# MicroMod-Artemis-ProcessorBoard.net
KiCad netlist of a schematic drawn in EAGLE
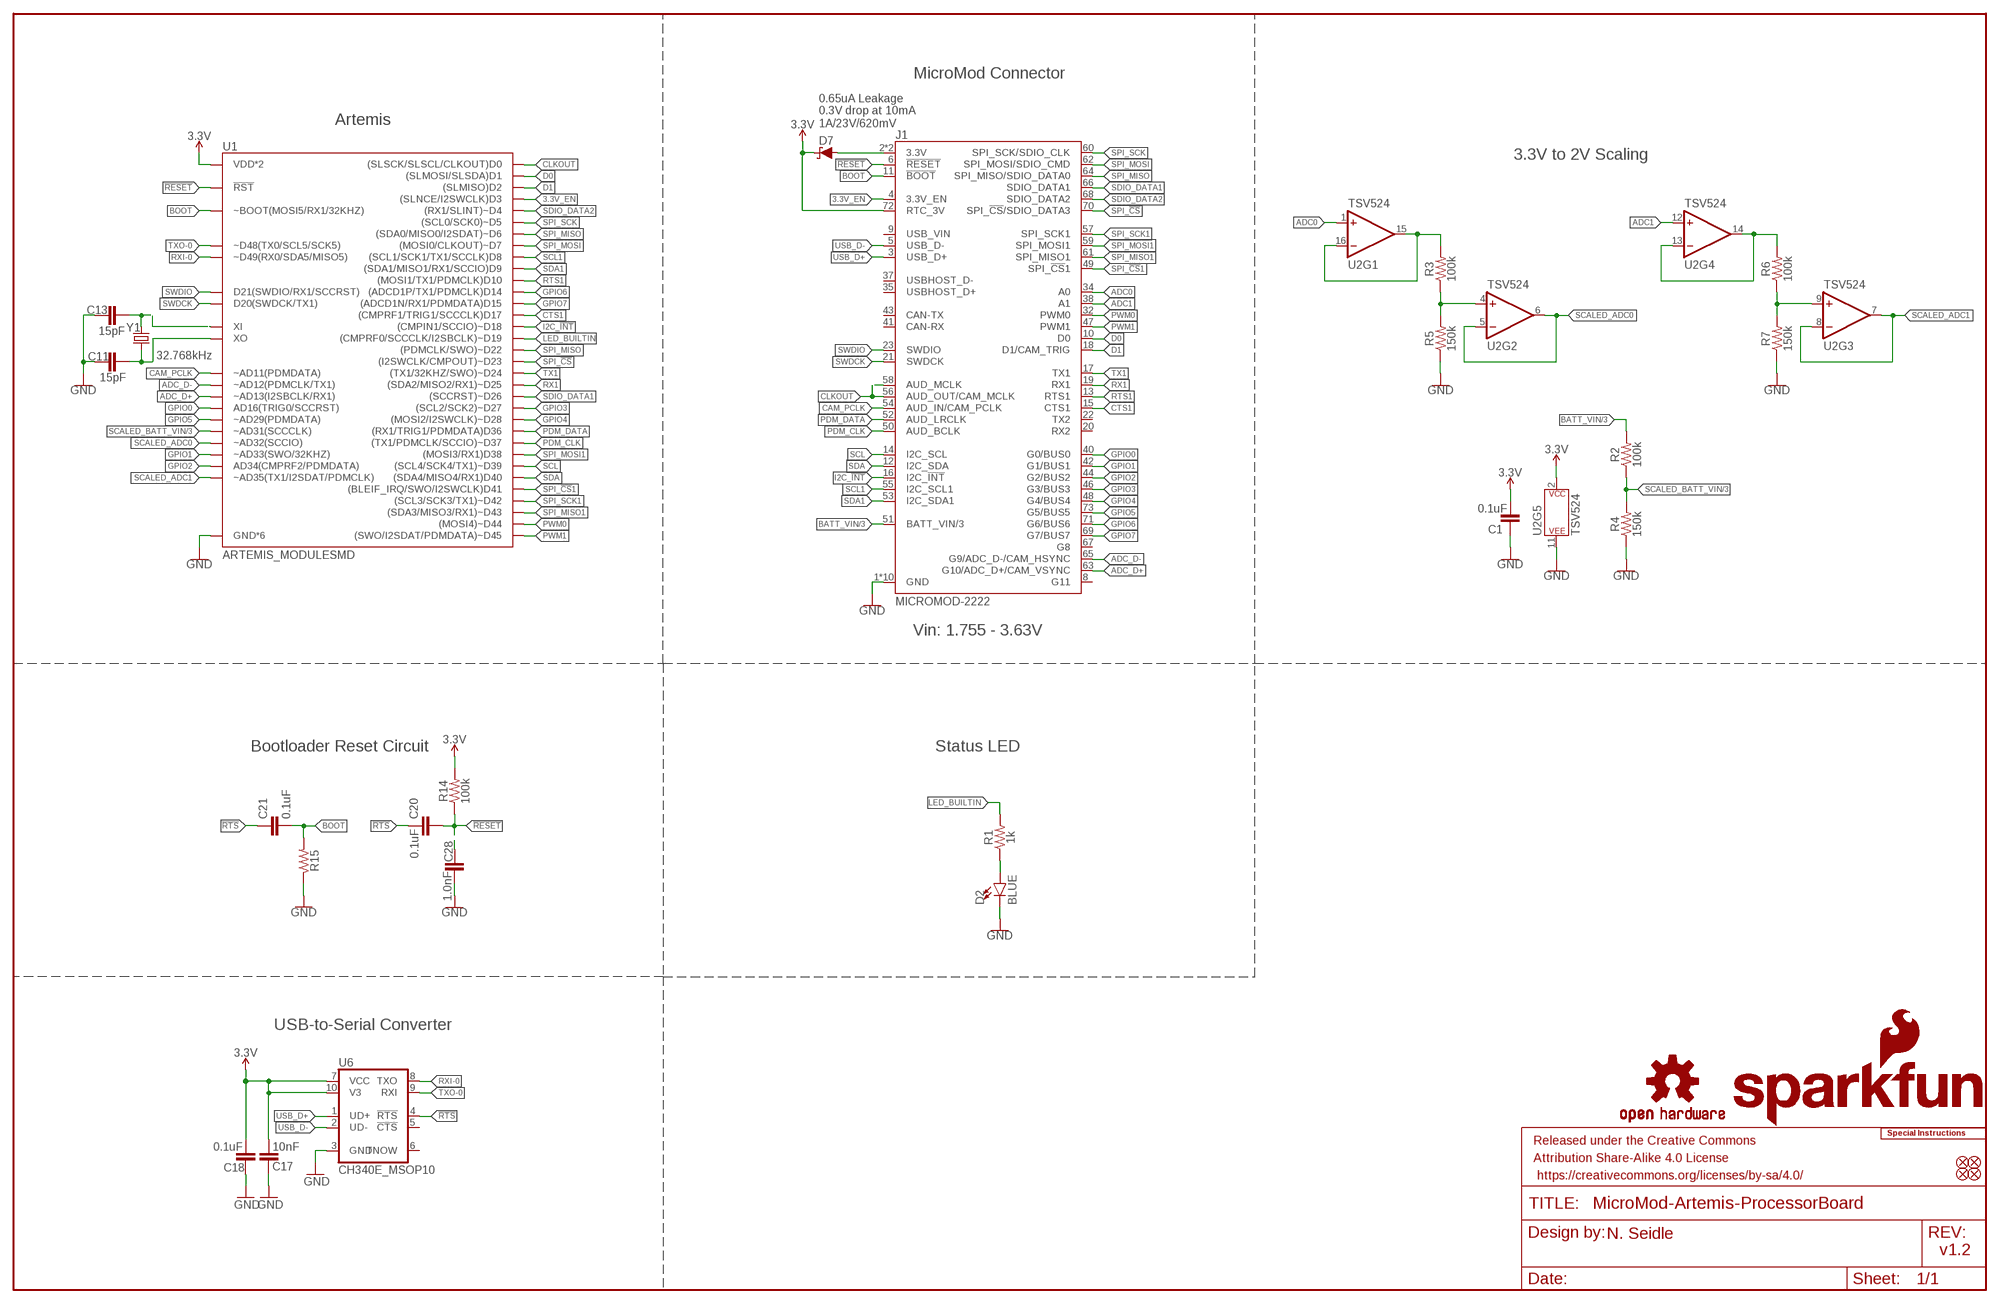
[diagram p0: schematic, sheet 1]

(export (version "E")
  (design (tool "Eeschema 10.0.6"))
  (components
    (comp (ref "C1")
      (value "0.1uF")
      (footprint "eagle-import:0402-TIGHT")
      (libsource (lib "eagle-import") (part "0.1UF-0402T-16V-10%"))
    )
    (comp (ref "C11")
      (value "15pF")
      (footprint "eagle-import:0402-TIGHT")
      (libsource (lib "eagle-import") (part "15PF-0402T-50V-5%"))
    )
    (comp (ref "C13")
      (value "15pF")
      (footprint "eagle-import:0402-TIGHT")
      (libsource (lib "eagle-import") (part "15PF-0402T-50V-5%"))
    )
    (comp (ref "C17")
      (value "10nF")
      (footprint "eagle-import:0402-TIGHT")
      (libsource (lib "eagle-import") (part "10NF-0402T-25V-10%"))
    )
    (comp (ref "C18")
      (value "0.1uF")
      (footprint "eagle-import:0402-TIGHT")
      (libsource (lib "eagle-import") (part "0.1UF-0402T-16V-10%"))
    )
    (comp (ref "C20")
      (value "0.1uF")
      (footprint "eagle-import:0402-TIGHT")
      (libsource (lib "eagle-import") (part "0.1UF-0402T-16V-10%"))
    )
    (comp (ref "C21")
      (value "0.1uF")
      (footprint "eagle-import:0402-TIGHT")
      (libsource (lib "eagle-import") (part "0.1UF-0402T-16V-10%"))
    )
    (comp (ref "C28")
      (value "1.0nF")
      (footprint "eagle-import:0402-TIGHT")
      (libsource (lib "eagle-import") (part "1.0NF/1000PF-0402_TIGHT-50V-10%"))
    )
    (comp (ref "D2")
      (value "BLUE")
      (footprint "eagle-import:LED-0603")
      (libsource (lib "eagle-import") (part "LED-BLUE0603"))
    )
    (comp (ref "D7")
      (value "1A/23V/620mV")
      (footprint "eagle-import:SOD-323")
      (libsource (lib "eagle-import") (part "DIODE-SCHOTTKY-BAT20J"))
    )
    (comp (ref "FD1")
      (value "FIDUCIALUFIDUCIAL")
      (footprint "eagle-import:FIDUCIAL-MICRO")
      (libsource (lib "eagle-import") (part "FIDUCIALUFIDUCIAL"))
    )
    (comp (ref "FD2")
      (value "FIDUCIALUFIDUCIAL")
      (footprint "eagle-import:FIDUCIAL-MICRO")
      (libsource (lib "eagle-import") (part "FIDUCIALUFIDUCIAL"))
    )
    (comp (ref "FD3")
      (value "FIDUCIALUFIDUCIAL")
      (footprint "eagle-import:FIDUCIAL-MICRO")
      (libsource (lib "eagle-import") (part "FIDUCIALUFIDUCIAL"))
    )
    (comp (ref "FD4")
      (value "FIDUCIALUFIDUCIAL")
      (footprint "eagle-import:FIDUCIAL-MICRO")
      (libsource (lib "eagle-import") (part "FIDUCIALUFIDUCIAL"))
    )
    (comp (ref "FRAME1")
      (value "FRAME-LEDGER")
      (footprint "eagle-import:CREATIVE_COMMONS")
      (libsource (lib "eagle-import") (part "FRAME-LEDGER"))
    )
    (comp (ref "J1")
      (value "MICROMOD-2222")
      (footprint "eagle-import:M.2-CARD-E-22")
      (libsource (lib "eagle-import") (part "MICROMOD-2222"))
    )
    (comp (ref "LOGO1")
      (value "SFE_LOGO_NAME_FLAME.1_INCH")
      (footprint "eagle-import:SFE_LOGO_NAME_FLAME_.1")
      (libsource (lib "eagle-import") (part "SFE_LOGO_NAME_FLAME.1_INCH"))
    )
    (comp (ref "LOGO2")
      (value "SFE_LOGO_FLAME.1_INCH")
      (footprint "eagle-import:SFE_LOGO_FLAME_.1")
      (libsource (lib "eagle-import") (part "SFE_LOGO_FLAME.1_INCH"))
    )
    (comp (ref "LOGO3")
      (value "OSHW-LOGOMINI")
      (footprint "eagle-import:OSHW-LOGO-MINI")
      (libsource (lib "eagle-import") (part "OSHW-LOGOMINI"))
    )
    (comp (ref "LOGO4")
      (value "SPECIAL_INSTRUCTIONS-ORDERING")
      (footprint "eagle-import:ORDERING_INSTRUCTIONS")
      (libsource (lib "eagle-import") (part "SPECIAL_INSTRUCTIONS-ORDERING"))
    )
    (comp (ref "R1")
      (value "1k")
      (footprint "eagle-import:0402-TIGHT")
      (libsource (lib "eagle-import") (part "1KOHM-0402T-1/16W-1%"))
    )
    (comp (ref "R2")
      (value "100k")
      (footprint "eagle-import:0402-TIGHT")
      (libsource (lib "eagle-import") (part "100KOHM-0402T-1/16W-1%"))
    )
    (comp (ref "R3")
      (value "100k")
      (footprint "eagle-import:0402-TIGHT")
      (libsource (lib "eagle-import") (part "100KOHM-0402T-1/16W-1%"))
    )
    (comp (ref "R4")
      (value "150k")
      (footprint "eagle-import:0402-TIGHT")
      (libsource (lib "eagle-import") (part "150KOHM-0402T-1/16W-1%"))
    )
    (comp (ref "R5")
      (value "150k")
      (footprint "eagle-import:0402-TIGHT")
      (libsource (lib "eagle-import") (part "150KOHM-0402T-1/16W-1%"))
    )
    (comp (ref "R6")
      (value "100k")
      (footprint "eagle-import:0402-TIGHT")
      (libsource (lib "eagle-import") (part "100KOHM-0402T-1/16W-1%"))
    )
    (comp (ref "R7")
      (value "150k")
      (footprint "eagle-import:0402-TIGHT")
      (libsource (lib "eagle-import") (part "150KOHM-0402T-1/16W-1%"))
    )
    (comp (ref "R14")
      (value "100k")
      (footprint "eagle-import:0402-TIGHT")
      (libsource (lib "eagle-import") (part "100KOHM-0402T-1/16W-1%"))
    )
    (comp (ref "R15")
      (value "220KOHM-0402T-1/16W-1%")
      (footprint "eagle-import:0402-TIGHT")
      (libsource (lib "eagle-import") (part "220KOHM-0402T-1/16W-1%"))
    )
    (comp (ref "U1")
      (value "ARTEMIS_MODULESMD")
      (footprint "eagle-import:ARTEMIS_FP")
      (libsource (lib "eagle-import") (part "ARTEMIS_MODULESMD"))
    )
    (comp (ref "U2")
      (value "TSV524")
      (footprint "eagle-import:QFN-16")
      (libsource (lib "eagle-import") (part "TSV524"))
    )
    (comp (ref "U6")
      (value "CH340E_MSOP10")
      (footprint "eagle-import:MSOP10")
      (libsource (lib "eagle-import") (part "CH340E_MSOP10"))
    )
    (comp (ref "Y1")
      (value "32.768kHz")
      (footprint "eagle-import:CRYSTAL-SMD-3.2X1.5MM")
      (libsource (lib "eagle-import") (part "CRYSTAL-32.768KHZSMD-3.2X1.5"))
    )
  )
  (nets
    (net (code "1") (name "/I2C_~{INT}") (class "Default")
      (node (ref "J1") (pin "16") (pinfunction "I2C_~{INT}_16") (pintype "bidirectional"))
      (node (ref "U1") (pin "~D18") (pinfunction "(CMPIN1/SCCIO)~{D18}_~D18") (pintype "bidirectional"))
    )
    (net (code "2") (name "/SPI_~{CS}") (class "Default")
      (node (ref "J1") (pin "70") (pinfunction "SPI_~{CS}/SDIO_DATA3_70") (pintype "bidirectional"))
      (node (ref "U1") (pin "~D23") (pinfunction "(I2SWCLK/CMPOUT)~{D23}_~D23") (pintype "bidirectional"))
    )
    (net (code "3") (name "/SPI_~{CS}1") (class "Default")
      (node (ref "J1") (pin "49") (pinfunction "SPI_~{CS}1_49") (pintype "bidirectional"))
      (node (ref "U1") (pin "D41") (pinfunction "(BLEIF_IRQ/SWO/I2SWCLK)D41_D41") (pintype "bidirectional"))
    )
    (net (code "4") (name "/~{RESET}") (class "Default")
      (node (ref "C20") (pin "2") (pinfunction "2_2") (pintype "passive"))
      (node (ref "C28") (pin "1") (pinfunction "1_1") (pintype "passive"))
      (node (ref "J1") (pin "6") (pinfunction "~{RESET}_6") (pintype "bidirectional"))
      (node (ref "R14") (pin "1") (pinfunction "1_1") (pintype "passive"))
      (node (ref "U1") (pin "~RST") (pinfunction "~{RST}_~RST") (pintype "bidirectional"))
    )
    (net (code "5") (name "/~{RTS}") (class "Default")
      (node (ref "C20") (pin "1") (pinfunction "1_1") (pintype "passive"))
      (node (ref "C21") (pin "1") (pinfunction "1_1") (pintype "passive"))
      (node (ref "U6") (pin "4") (pinfunction "~{RTS}_4") (pintype "bidirectional"))
    )
    (net (code "6") (name "3.3V") (class "Default")
      (node (ref "C1") (pin "1") (pinfunction "1_1") (pintype "passive"))
      (node (ref "C17") (pin "1") (pinfunction "1_1") (pintype "passive"))
      (node (ref "C18") (pin "1") (pinfunction "1_1") (pintype "passive"))
      (node (ref "D7") (pin "C") (pinfunction "C_C") (pintype "passive"))
      (node (ref "J1") (pin "72") (pinfunction "RTC_3V_72") (pintype "bidirectional"))
      (node (ref "R14") (pin "2") (pinfunction "2_2") (pintype "passive"))
      (node (ref "U1") (pin "VDD@36") (pinfunction "VDD*2_VDD@36") (pintype "bidirectional"))
      (node (ref "U1") (pin "VDD@37") (pinfunction "VDD*2_VDD@37") (pintype "bidirectional"))
      (node (ref "U2") (pin "2") (pinfunction "V+_2") (pintype "bidirectional"))
      (node (ref "U6") (pin "10") (pinfunction "V3_10") (pintype "bidirectional"))
      (node (ref "U6") (pin "7") (pinfunction "VCC_7") (pintype "bidirectional"))
    )
    (net (code "7") (name "3.3V_EN") (class "Default")
      (node (ref "J1") (pin "4") (pinfunction "3.3V_EN_4") (pintype "bidirectional"))
      (node (ref "U1") (pin "D3") (pinfunction "(SLNCE/I2SWCLK)D3_D3") (pintype "bidirectional"))
    )
    (net (code "8") (name "ADC0") (class "Default")
      (node (ref "J1") (pin "34") (pinfunction "A0_34") (pintype "bidirectional"))
      (node (ref "U2") (pin "1") (pinfunction "+IN_1") (pintype "input"))
    )
    (net (code "9") (name "ADC1") (class "Default")
      (node (ref "J1") (pin "38") (pinfunction "A1_38") (pintype "bidirectional"))
      (node (ref "U2") (pin "12") (pinfunction "+IN_12") (pintype "input"))
    )
    (net (code "10") (name "ADC_D+") (class "Default")
      (node (ref "J1") (pin "63") (pinfunction "G10/ADC_D+/CAM_VSYNC_63") (pintype "bidirectional"))
      (node (ref "U1") (pin "~AD13") (pinfunction "~{AD13(I2SBCLK/RX1})_~AD13") (pintype "bidirectional"))
    )
    (net (code "11") (name "ADC_D-") (class "Default")
      (node (ref "J1") (pin "65") (pinfunction "G9/ADC_D-/CAM_HSYNC_65") (pintype "bidirectional"))
      (node (ref "U1") (pin "~AD12") (pinfunction "~{AD12(PDMCLK/TX1})_~AD12") (pintype "bidirectional"))
    )
    (net (code "12") (name "BATT_VIN{slash}3") (class "Default")
      (node (ref "J1") (pin "51") (pinfunction "BATT_VIN/3_51") (pintype "bidirectional"))
      (node (ref "R2") (pin "2") (pinfunction "2_2") (pintype "passive"))
    )
    (net (code "13") (name "BOOT") (class "Default")
      (node (ref "C21") (pin "2") (pinfunction "2_2") (pintype "passive"))
      (node (ref "J1") (pin "11") (pinfunction "~{BOOT}_11") (pintype "bidirectional"))
      (node (ref "R15") (pin "2") (pinfunction "2_2") (pintype "passive"))
      (node (ref "U1") (pin "BOOT") (pinfunction "~{BOOT(MOSI5/RX1/32KHZ})_BOOT") (pintype "bidirectional"))
    )
    (net (code "14") (name "CAM_PCLK") (class "Default")
      (node (ref "J1") (pin "54") (pinfunction "AUD_IN/CAM_PCLK_54") (pintype "bidirectional"))
      (node (ref "U1") (pin "~AD11") (pinfunction "~{AD11(PDMDATA})_~AD11") (pintype "bidirectional"))
    )
    (net (code "15") (name "CLKOUT") (class "Default")
      (node (ref "J1") (pin "56") (pinfunction "AUD_OUT/CAM_MCLK_56") (pintype "bidirectional"))
      (node (ref "J1") (pin "58") (pinfunction "AUD_MCLK_58") (pintype "bidirectional"))
      (node (ref "U1") (pin "D0") (pinfunction "(SLSCK/SLSCL/CLKOUT)D0_D0") (pintype "bidirectional"))
    )
    (net (code "16") (name "CTS1") (class "Default")
      (node (ref "J1") (pin "15") (pinfunction "CTS1_15") (pintype "bidirectional"))
      (node (ref "U1") (pin "D17") (pinfunction "(CMPRF1/TRIG1/SCCCLK)D17_D17") (pintype "bidirectional"))
    )
    (net (code "17") (name "D0") (class "Default")
      (node (ref "J1") (pin "10") (pinfunction "D0_10") (pintype "bidirectional"))
      (node (ref "U1") (pin "D1") (pinfunction "(SLMOSI/SLSDA)D1_D1") (pintype "bidirectional"))
    )
    (net (code "18") (name "D1") (class "Default")
      (node (ref "J1") (pin "18") (pinfunction "D1/CAM_TRIG_18") (pintype "bidirectional"))
      (node (ref "U1") (pin "D2") (pinfunction "(SLMISO)D2_D2") (pintype "bidirectional"))
    )
    (net (code "19") (name "GND") (class "Default")
      (node (ref "C1") (pin "2") (pinfunction "2_2") (pintype "passive"))
      (node (ref "C11") (pin "1") (pinfunction "1_1") (pintype "passive"))
      (node (ref "C13") (pin "1") (pinfunction "1_1") (pintype "passive"))
      (node (ref "C17") (pin "2") (pinfunction "2_2") (pintype "passive"))
      (node (ref "C18") (pin "2") (pinfunction "2_2") (pintype "passive"))
      (node (ref "C28") (pin "2") (pinfunction "2_2") (pintype "passive"))
      (node (ref "D2") (pin "C") (pinfunction "C_C") (pintype "passive"))
      (node (ref "J1") (pin "1") (pinfunction "GND_1") (pintype "bidirectional"))
      (node (ref "J1") (pin "33") (pinfunction "GND_33") (pintype "bidirectional"))
      (node (ref "J1") (pin "36") (pinfunction "GND_36") (pintype "bidirectional"))
      (node (ref "J1") (pin "39") (pinfunction "GND_39") (pintype "bidirectional"))
      (node (ref "J1") (pin "45") (pinfunction "GND_45") (pintype "bidirectional"))
      (node (ref "J1") (pin "7") (pinfunction "GND_7") (pintype "bidirectional"))
      (node (ref "J1") (pin "75") (pinfunction "GND_75") (pintype "bidirectional"))
      (node (ref "J1") (pin "GND1") (pinfunction "GND_GND1") (pintype "bidirectional"))
      (node (ref "J1") (pin "GND2") (pinfunction "GND_GND2") (pintype "bidirectional"))
      (node (ref "J1") (pin "GND3") (pinfunction "GND_GND3") (pintype "bidirectional"))
      (node (ref "R15") (pin "1") (pinfunction "1_1") (pintype "passive"))
      (node (ref "R4") (pin "1") (pinfunction "1_1") (pintype "passive"))
      (node (ref "R5") (pin "1") (pinfunction "1_1") (pintype "passive"))
      (node (ref "R7") (pin "1") (pinfunction "1_1") (pintype "passive"))
      (node (ref "U1") (pin "GND@1") (pinfunction "GND*6_GND@1") (pintype "bidirectional"))
      (node (ref "U1") (pin "GND@22") (pinfunction "GND*6_GND@22") (pintype "bidirectional"))
      (node (ref "U1") (pin "GND@38") (pinfunction "GND*6_GND@38") (pintype "bidirectional"))
      (node (ref "U1") (pin "GND@39") (pinfunction "GND*6_GND@39") (pintype "bidirectional"))
      (node (ref "U1") (pin "GND@47") (pinfunction "GND*6_GND@47") (pintype "bidirectional"))
      (node (ref "U1") (pin "GND@59") (pinfunction "GND*6_GND@59") (pintype "bidirectional"))
      (node (ref "U2") (pin "11") (pinfunction "V-_11") (pintype "bidirectional"))
      (node (ref "U6") (pin "3") (pinfunction "GND_3") (pintype "bidirectional"))
    )
    (net (code "20") (name "GPIO0") (class "Default")
      (node (ref "J1") (pin "40") (pinfunction "G0/BUS0_40") (pintype "bidirectional"))
      (node (ref "U1") (pin "AD16") (pinfunction "AD16(TRIG0/SCCRST)_AD16") (pintype "bidirectional"))
    )
    (net (code "21") (name "GPIO1") (class "Default")
      (node (ref "J1") (pin "42") (pinfunction "G1/BUS1_42") (pintype "bidirectional"))
      (node (ref "U1") (pin "~AD33/SWO") (pinfunction "~{AD33(SWO/32KHZ})_~AD33/SWO") (pintype "bidirectional"))
    )
    (net (code "22") (name "GPIO2") (class "Default")
      (node (ref "J1") (pin "44") (pinfunction "G2/BUS2_44") (pintype "bidirectional"))
      (node (ref "U1") (pin "AD34") (pinfunction "AD34(CMPRF2/PDMDATA)_AD34") (pintype "bidirectional"))
    )
    (net (code "23") (name "GPIO3") (class "Default")
      (node (ref "J1") (pin "46") (pinfunction "G3/BUS3_46") (pintype "bidirectional"))
      (node (ref "U1") (pin "~D27") (pinfunction "(SCL2/SCK2)~{D27}_~D27") (pintype "bidirectional"))
    )
    (net (code "24") (name "GPIO4") (class "Default")
      (node (ref "J1") (pin "48") (pinfunction "G4/BUS4_48") (pintype "bidirectional"))
      (node (ref "U1") (pin "~D28") (pinfunction "(MOSI2/I2SWCLK)~{D28}_~D28") (pintype "bidirectional"))
    )
    (net (code "25") (name "GPIO5") (class "Default")
      (node (ref "J1") (pin "73") (pinfunction "G5/BUS5_73") (pintype "bidirectional"))
      (node (ref "U1") (pin "~AD29") (pinfunction "~{AD29(PDMDATA})_~AD29") (pintype "bidirectional"))
    )
    (net (code "26") (name "GPIO6") (class "Default")
      (node (ref "J1") (pin "71") (pinfunction "G6/BUS6_71") (pintype "bidirectional"))
      (node (ref "U1") (pin "D14") (pinfunction "(ADCD1P/TX1/PDMCLK)D14_D14") (pintype "bidirectional"))
    )
    (net (code "27") (name "GPIO7") (class "Default")
      (node (ref "J1") (pin "69") (pinfunction "G7/BUS7_69") (pintype "bidirectional"))
      (node (ref "U1") (pin "D15") (pinfunction "(ADCD1N/RX1/PDMDATA)D15_D15") (pintype "bidirectional"))
    )
    (net (code "28") (name "LED_BUILTIN") (class "Default")
      (node (ref "R1") (pin "2") (pinfunction "2_2") (pintype "passive"))
      (node (ref "U1") (pin "~D19") (pinfunction "(CMPRF0/SCCCLK/I2SBCLK)~{D19}_~D19") (pintype "bidirectional"))
    )
    (net (code "29") (name "Net-(D2-PadA)") (class "Default")
      (node (ref "D2") (pin "A") (pinfunction "A_A") (pintype "passive"))
      (node (ref "R1") (pin "1") (pinfunction "1_1") (pintype "passive"))
    )
    (net (code "30") (name "Net-(D7-PadA)") (class "Default")
      (node (ref "D7") (pin "A") (pinfunction "A_A") (pintype "passive"))
      (node (ref "J1") (pin "2") (pinfunction "3.3V_2") (pintype "bidirectional"))
      (node (ref "J1") (pin "74") (pinfunction "3.3V_74") (pintype "bidirectional"))
    )
    (net (code "31") (name "Net-(U2A--IN)") (class "Default")
      (node (ref "R3") (pin "2") (pinfunction "2_2") (pintype "passive"))
      (node (ref "U2") (pin "15") (pinfunction "OUT_15") (pintype "output"))
      (node (ref "U2") (pin "16") (pinfunction "-IN_16") (pintype "input"))
    )
    (net (code "32") (name "Net-(U2B-+IN)") (class "Default")
      (node (ref "R3") (pin "1") (pinfunction "1_1") (pintype "passive"))
      (node (ref "R5") (pin "2") (pinfunction "2_2") (pintype "passive"))
      (node (ref "U2") (pin "4") (pinfunction "+IN_4") (pintype "input"))
    )
    (net (code "33") (name "Net-(U2C-+IN)") (class "Default")
      (node (ref "R6") (pin "1") (pinfunction "1_1") (pintype "passive"))
      (node (ref "R7") (pin "2") (pinfunction "2_2") (pintype "passive"))
      (node (ref "U2") (pin "9") (pinfunction "+IN_9") (pintype "input"))
    )
    (net (code "34") (name "Net-(U2D--IN)") (class "Default")
      (node (ref "R6") (pin "2") (pinfunction "2_2") (pintype "passive"))
      (node (ref "U2") (pin "13") (pinfunction "-IN_13") (pintype "input"))
      (node (ref "U2") (pin "14") (pinfunction "OUT_14") (pintype "output"))
    )
    (net (code "35") (name "Net-(Y1-1)") (class "Default")
      (node (ref "C13") (pin "2") (pinfunction "2_2") (pintype "passive"))
      (node (ref "Y1") (pin "P$1") (pinfunction "1_P$1") (pintype "passive"))
    )
    (net (code "36") (name "Net-(Y1-2)") (class "Default")
      (node (ref "C11") (pin "2") (pinfunction "2_2") (pintype "passive"))
      (node (ref "U1") (pin "XO") (pinfunction "XO_XO") (pintype "bidirectional"))
      (node (ref "Y1") (pin "P$2") (pinfunction "2_P$2") (pintype "passive"))
    )
    (net (code "37") (name "PDM_CLK") (class "Default")
      (node (ref "J1") (pin "50") (pinfunction "AUD_BCLK_50") (pintype "bidirectional"))
      (node (ref "U1") (pin "~D37") (pinfunction "(TX1/PDMCLK/SCCIO)~{D37}_~D37") (pintype "bidirectional"))
    )
    (net (code "38") (name "PDM_DATA") (class "Default")
      (node (ref "J1") (pin "52") (pinfunction "AUD_LRCLK_52") (pintype "bidirectional"))
      (node (ref "U1") (pin "D36") (pinfunction "(RX1/TRIG1/PDMDATA)D36_D36") (pintype "bidirectional"))
    )
    (net (code "39") (name "PWM0") (class "Default")
      (node (ref "J1") (pin "32") (pinfunction "PWM0_32") (pintype "bidirectional"))
      (node (ref "U1") (pin "~D44") (pinfunction "(MOSI4)~{D44}_~D44") (pintype "bidirectional"))
    )
    (net (code "40") (name "PWM1") (class "Default")
      (node (ref "J1") (pin "47") (pinfunction "PWM1_47") (pintype "bidirectional"))
      (node (ref "U1") (pin "~D45") (pinfunction "(SWO/I2SDAT/PDMDATA)~{D45}_~D45") (pintype "bidirectional"))
    )
    (net (code "41") (name "RTS1") (class "Default")
      (node (ref "J1") (pin "13") (pinfunction "RTS1_13") (pintype "bidirectional"))
      (node (ref "U1") (pin "D10") (pinfunction "(MOSI1/TX1/PDMCLK)D10_D10") (pintype "bidirectional"))
    )
    (net (code "42") (name "RX1") (class "Default")
      (node (ref "J1") (pin "19") (pinfunction "RX1_19") (pintype "bidirectional"))
      (node (ref "U1") (pin "~D25") (pinfunction "(SDA2/MISO2/RX1)~{D25}_~D25") (pintype "bidirectional"))
    )
    (net (code "43") (name "RXI-0") (class "Default")
      (node (ref "U1") (pin "RXI-0") (pinfunction "~{D49(RX0/SDA5/MISO5})_RXI-0") (pintype "bidirectional"))
      (node (ref "U6") (pin "8") (pinfunction "TXO_8") (pintype "bidirectional"))
    )
    (net (code "44") (name "SCALED_ADC0") (class "Default")
      (node (ref "U1") (pin "~AD32") (pinfunction "~{AD32(SCCIO})_~AD32") (pintype "bidirectional"))
      (node (ref "U2") (pin "5") (pinfunction "-IN_5") (pintype "input"))
      (node (ref "U2") (pin "6") (pinfunction "OUT_6") (pintype "output"))
    )
    (net (code "45") (name "SCALED_ADC1") (class "Default")
      (node (ref "U1") (pin "~AD35") (pinfunction "~{AD35(TX1/I2SDAT/PDMCLK})_~AD35") (pintype "bidirectional"))
      (node (ref "U2") (pin "7") (pinfunction "OUT_7") (pintype "output"))
      (node (ref "U2") (pin "8") (pinfunction "-IN_8") (pintype "input"))
    )
    (net (code "46") (name "SCALED_BATT_VIN{slash}3") (class "Default")
      (node (ref "R2") (pin "1") (pinfunction "1_1") (pintype "passive"))
      (node (ref "R4") (pin "2") (pinfunction "2_2") (pintype "passive"))
      (node (ref "U1") (pin "~AD31") (pinfunction "~{AD31(SCCCLK})_~AD31") (pintype "bidirectional"))
    )
    (net (code "47") (name "SCL") (class "Default")
      (node (ref "J1") (pin "14") (pinfunction "I2C_SCL_14") (pintype "bidirectional"))
      (node (ref "U1") (pin "~D39") (pinfunction "(SCL4/SCK4/TX1)~{D39}_~D39") (pintype "bidirectional"))
    )
    (net (code "48") (name "SCL1") (class "Default")
      (node (ref "J1") (pin "55") (pinfunction "I2C_SCL1_55") (pintype "bidirectional"))
      (node (ref "U1") (pin "D8") (pinfunction "(SCL1/SCK1/TX1/SCCLK)D8_D8") (pintype "bidirectional"))
    )
    (net (code "49") (name "SDA") (class "Default")
      (node (ref "J1") (pin "12") (pinfunction "I2C_SDA_12") (pintype "bidirectional"))
      (node (ref "U1") (pin "D40") (pinfunction "(SDA4/MISO4/RX1)D40_D40") (pintype "bidirectional"))
    )
    (net (code "50") (name "SDA1") (class "Default")
      (node (ref "J1") (pin "53") (pinfunction "I2C_SDA1_53") (pintype "bidirectional"))
      (node (ref "U1") (pin "D9") (pinfunction "(SDA1/MISO1/RX1/SCCIO)D9_D9") (pintype "bidirectional"))
    )
    (net (code "51") (name "SDIO_DATA1") (class "Default")
      (node (ref "J1") (pin "66") (pinfunction "SDIO_DATA1_66") (pintype "bidirectional"))
      (node (ref "U1") (pin "~D26") (pinfunction "(SCCRST)~{D26}_~D26") (pintype "bidirectional"))
    )
    (net (code "52") (name "SDIO_DATA2") (class "Default")
      (node (ref "J1") (pin "68") (pinfunction "SDIO_DATA2_68") (pintype "bidirectional"))
      (node (ref "U1") (pin "~D4") (pinfunction "(RX1/SLINT)~{D4}_~D4") (pintype "bidirectional"))
    )
    (net (code "53") (name "SPI_MISO") (class "Default")
      (node (ref "J1") (pin "64") (pinfunction "SPI_MISO/SDIO_DATA0_64") (pintype "bidirectional"))
      (node (ref "U1") (pin "~D22") (pinfunction "(PDMCLK/SWO)~{D22}_~D22") (pintype "bidirectional"))
      (node (ref "U1") (pin "~D6") (pinfunction "(SDA0/MISO0/I2SDAT)~{D6}_~D6") (pintype "bidirectional"))
    )
    (net (code "54") (name "SPI_MISO1") (class "Default")
      (node (ref "J1") (pin "61") (pinfunction "SPI_MISO1_61") (pintype "bidirectional"))
      (node (ref "U1") (pin "~D43") (pinfunction "(SDA3/MISO3/RX1)~{D43}_~D43") (pintype "bidirectional"))
    )
    (net (code "55") (name "SPI_MOSI") (class "Default")
      (node (ref "J1") (pin "62") (pinfunction "SPI_MOSI/SDIO_CMD_62") (pintype "bidirectional"))
      (node (ref "U1") (pin "D7") (pinfunction "(MOSI0/CLKOUT)~{D7}_D7") (pintype "bidirectional"))
    )
    (net (code "56") (name "SPI_MOSI1") (class "Default")
      (node (ref "J1") (pin "59") (pinfunction "SPI_MOSI1_59") (pintype "bidirectional"))
      (node (ref "U1") (pin "D38") (pinfunction "(MOSI3/RX1)D38_D38") (pintype "bidirectional"))
    )
    (net (code "57") (name "SPI_SCK") (class "Default")
      (node (ref "J1") (pin "60") (pinfunction "SPI_SCK/SDIO_CLK_60") (pintype "bidirectional"))
      (node (ref "U1") (pin "~D5") (pinfunction "(SCL0/SCK0)~{D5}_~D5") (pintype "bidirectional"))
    )
    (net (code "58") (name "SPI_SCK1") (class "Default")
      (node (ref "J1") (pin "57") (pinfunction "SPI_SCK1_57") (pintype "bidirectional"))
      (node (ref "U1") (pin "~D42") (pinfunction "(SCL3/SCK3/TX1)~{D42}_~D42") (pintype "bidirectional"))
    )
    (net (code "59") (name "SWDCK") (class "Default")
      (node (ref "J1") (pin "21") (pinfunction "SWDCK_21") (pintype "bidirectional"))
      (node (ref "U1") (pin "SWDCK") (pinfunction "D20(SWDCK/TX1)_SWDCK") (pintype "bidirectional"))
    )
    (net (code "60") (name "SWDIO") (class "Default")
      (node (ref "J1") (pin "23") (pinfunction "SWDIO_23") (pintype "bidirectional"))
      (node (ref "U1") (pin "SWDIO") (pinfunction "D21(SWDIO/RX1/SCCRST)_SWDIO") (pintype "bidirectional"))
    )
    (net (code "61") (name "TX1") (class "Default")
      (node (ref "J1") (pin "17") (pinfunction "TX1_17") (pintype "bidirectional"))
      (node (ref "U1") (pin "~D24") (pinfunction "(TX1/32KHZ/SWO)~{D24}_~D24") (pintype "bidirectional"))
    )
    (net (code "62") (name "TXO-0") (class "Default")
      (node (ref "U1") (pin "TXO-0") (pinfunction "~{D48(TX0/SCL5/SCK5})_TXO-0") (pintype "bidirectional"))
      (node (ref "U6") (pin "9") (pinfunction "RXI_9") (pintype "bidirectional"))
    )
    (net (code "63") (name "USB_D+") (class "Default")
      (node (ref "J1") (pin "3") (pinfunction "USB_D+_3") (pintype "bidirectional"))
      (node (ref "U6") (pin "1") (pinfunction "UD+_1") (pintype "bidirectional"))
    )
    (net (code "64") (name "USB_D-") (class "Default")
      (node (ref "J1") (pin "5") (pinfunction "USB_D-_5") (pintype "bidirectional"))
      (node (ref "U6") (pin "2") (pinfunction "UD-_2") (pintype "bidirectional"))
    )
    (net (code "65") (name "unconnected-(J1-CAN-RX-Pad41)") (class "Default")
      (node (ref "J1") (pin "41") (pinfunction "CAN-RX_41") (pintype "bidirectional"))
    )
    (net (code "66") (name "unconnected-(J1-CAN-TX-Pad43)") (class "Default")
      (node (ref "J1") (pin "43") (pinfunction "CAN-TX_43") (pintype "bidirectional"))
    )
    (net (code "67") (name "unconnected-(J1-G8-Pad67)") (class "Default")
      (node (ref "J1") (pin "67") (pinfunction "G8_67") (pintype "bidirectional"))
    )
    (net (code "68") (name "unconnected-(J1-G11-Pad8)") (class "Default")
      (node (ref "J1") (pin "8") (pinfunction "G11_8") (pintype "bidirectional"))
    )
    (net (code "69") (name "unconnected-(J1-RX2-Pad20)") (class "Default")
      (node (ref "J1") (pin "20") (pinfunction "RX2_20") (pintype "bidirectional"))
    )
    (net (code "70") (name "unconnected-(J1-TX2-Pad22)") (class "Default")
      (node (ref "J1") (pin "22") (pinfunction "TX2_22") (pintype "bidirectional"))
    )
    (net (code "71") (name "unconnected-(J1-USBHOST_D+-Pad35)") (class "Default")
      (node (ref "J1") (pin "35") (pinfunction "USBHOST_D+_35") (pintype "bidirectional"))
    )
    (net (code "72") (name "unconnected-(J1-USBHOST_D--Pad37)") (class "Default")
      (node (ref "J1") (pin "37") (pinfunction "USBHOST_D-_37") (pintype "bidirectional"))
    )
    (net (code "73") (name "unconnected-(J1-USB_VIN-Pad9)") (class "Default")
      (node (ref "J1") (pin "9") (pinfunction "USB_VIN_9") (pintype "bidirectional"))
    )
    (net (code "74") (name "unconnected-(U1-PadXI)") (class "Default")
      (node (ref "U1") (pin "XI") (pinfunction "XI_XI") (pintype "bidirectional"))
    )
    (net (code "75") (name "unconnected-(U6-TNOW-Pad6)") (class "Default")
      (node (ref "U6") (pin "6") (pinfunction "TNOW_6") (pintype "bidirectional"))
    )
    (net (code "76") (name "unconnected-(U6-~{CTS}-Pad5)") (class "Default")
      (node (ref "U6") (pin "5") (pinfunction "~{CTS}_5") (pintype "bidirectional"))
    )
  )
)
